# ap-pam-v3_1.net
KiCad netlist of a schematic drawn in Altium Designer
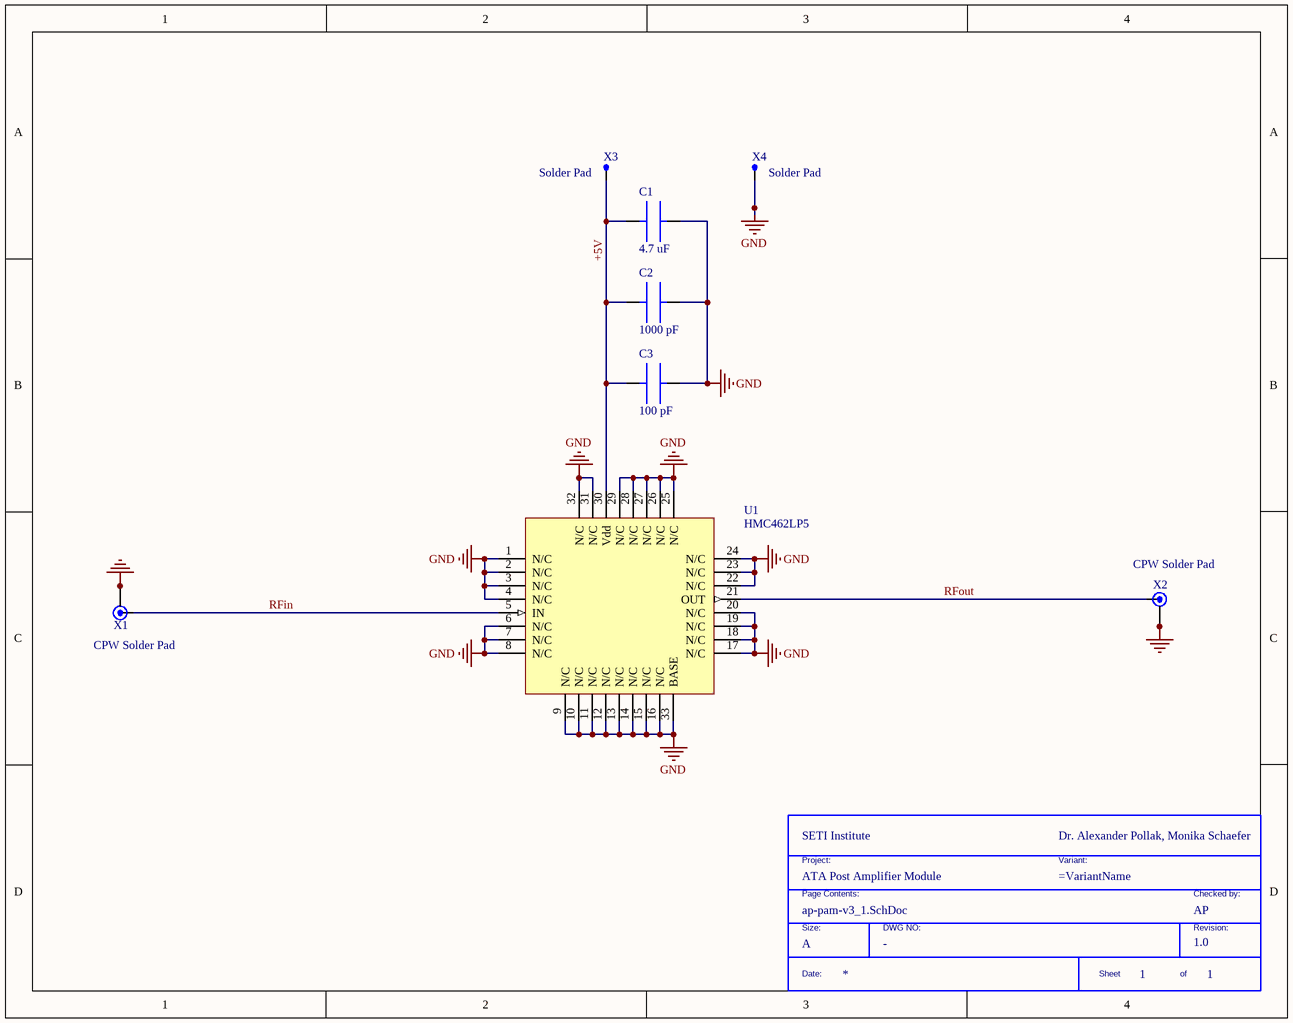
[diagram p0: ap-pam-v3_1.SchDoc]

(export (version "E")
  (design (tool "Eeschema 10.0.6"))
  (components
    (comp (ref "*")
      (value "~")
      (description "Standard Title Block")
      (fields (field (name "DWG NO") "-") (field (name "SIZE") "A") (field (name "CHECKED BY") "AP"))
      (libsource (lib "ap-pam") (part "TitleBlock"))
    )
    (comp (ref "C1")
      (value "4.7 uF")
      (footprint "C4_7uF")
      (fields
        (field (name "MANUFACTURER") "Vishay Sprague")
        (field (name "MANUFACTURER PART NUMBER") "TH3A475K010C2900")
      )
      (libsource (lib "ap-pam") (part "TH3A475K010C2900"))
    )
    (comp (ref "C2")
      (value "1000 pF")
      (footprint "C1000pF")
      (fields
        (field (name "MANUFACTURER") "Murata")
        (field (name "MANUFACTURER PART NUMBER") "GCM1885C1H102FA16D")
      )
      (libsource (lib "ap-pam") (part "GCM1885C1H102FA16D"))
    )
    (comp (ref "C3")
      (value "100 pF")
      (footprint "C100pF")
      (description "Multilayer Ceramic Capacitors MLCC - SMD/SMT 100 pF 100 VDC 1% 0402 C0G (NP0)")
      (fields
        (field (name "MANUFACTURER") "Murata")
        (field (name "MANUFACTURER PART NUMBER") "GRM1555C2A101FA01D")
      )
      (libsource (lib "ap-pam") (part "GRM1555C2A101FA01D"))
    )
    (comp (ref "U1")
      (value "HMC462LP5")
      (footprint "HMC462LP5E")
      (description "Wide Band Low Power Amplifier, 2000MHz Min, 20000MHz Max, 1 Func, GAAS")
      (fields (field (name "MANUFACTURER") "Analog Devices"))
      (libsource (lib "ap-pam") (part "HMC462LP5"))
    )
    (comp (ref "X1")
      (value "CPW Solder Pad")
      (footprint "CPW Edge Connector")
      (description "Solder pad for RF Coplanar Waveguide Rogers 4350B Thickness 0.020\" Copper 1oz")
      (libsource (lib "ap-pam") (part "RF  CPW Solder Pad"))
    )
    (comp (ref "X2")
      (value "CPW Solder Pad")
      (footprint "CPW Edge Connector")
      (description "Solder pad for RF Coplanar Waveguide Rogers 4350B Thickness 0.020\" Copper 1oz")
      (libsource (lib "ap-pam") (part "RF  CPW Solder Pad"))
    )
    (comp (ref "X3")
      (value "Solder Pad")
      (footprint "Solder Pad")
      (description "Pad to solder wires to")
      (libsource (lib "ap-pam") (part "Solder Pad"))
    )
    (comp (ref "X4")
      (value "Solder Pad")
      (footprint "Solder Pad")
      (description "Pad to solder wires to")
      (libsource (lib "ap-pam") (part "Solder Pad"))
    )
  )
  (nets
    (net (code "1") (name "/+5V") (class "Default")
      (node (ref "C1") (pin "1") (pinfunction "1_1") (pintype "passive"))
      (node (ref "C2") (pin "2") (pinfunction "2_2") (pintype "passive"))
      (node (ref "C3") (pin "2") (pinfunction "2_2") (pintype "passive"))
      (node (ref "U1") (pin "30") (pinfunction "Vdd_30") (pintype "power_in"))
      (node (ref "X3") (pin "1") (pinfunction "1_1") (pintype "passive"))
    )
    (net (code "2") (name "/RFin") (class "Default")
      (node (ref "U1") (pin "5") (pinfunction "IN_5") (pintype "input"))
      (node (ref "X1") (pin "1") (pinfunction "1_1") (pintype "passive"))
    )
    (net (code "3") (name "/RFout") (class "Default")
      (node (ref "U1") (pin "21") (pinfunction "OUT_21") (pintype "output"))
      (node (ref "X2") (pin "1") (pinfunction "1_1") (pintype "passive"))
    )
    (net (code "4") (name "GND") (class "Default")
      (node (ref "C1") (pin "2") (pinfunction "2_2") (pintype "passive"))
      (node (ref "C2") (pin "1") (pinfunction "1_1") (pintype "passive"))
      (node (ref "C3") (pin "1") (pinfunction "1_1") (pintype "passive"))
      (node (ref "U1") (pin "1") (pinfunction "N/C_1") (pintype "passive"))
      (node (ref "U1") (pin "10") (pinfunction "N/C_10") (pintype "passive"))
      (node (ref "U1") (pin "11") (pinfunction "N/C_11") (pintype "passive"))
      (node (ref "U1") (pin "12") (pinfunction "N/C_12") (pintype "passive"))
      (node (ref "U1") (pin "13") (pinfunction "N/C_13") (pintype "passive"))
      (node (ref "U1") (pin "14") (pinfunction "N/C_14") (pintype "passive"))
      (node (ref "U1") (pin "15") (pinfunction "N/C_15") (pintype "passive"))
      (node (ref "U1") (pin "16") (pinfunction "N/C_16") (pintype "passive"))
      (node (ref "U1") (pin "17") (pinfunction "N/C_17") (pintype "passive"))
      (node (ref "U1") (pin "18") (pinfunction "N/C_18") (pintype "passive"))
      (node (ref "U1") (pin "19") (pinfunction "N/C_19") (pintype "passive"))
      (node (ref "U1") (pin "2") (pinfunction "N/C_2") (pintype "passive"))
      (node (ref "U1") (pin "20") (pinfunction "N/C_20") (pintype "passive"))
      (node (ref "U1") (pin "22") (pinfunction "N/C_22") (pintype "passive"))
      (node (ref "U1") (pin "23") (pinfunction "N/C_23") (pintype "passive"))
      (node (ref "U1") (pin "24") (pinfunction "N/C_24") (pintype "passive"))
      (node (ref "U1") (pin "25") (pinfunction "N/C_25") (pintype "passive"))
      (node (ref "U1") (pin "26") (pinfunction "N/C_26") (pintype "passive"))
      (node (ref "U1") (pin "27") (pinfunction "N/C_27") (pintype "passive"))
      (node (ref "U1") (pin "28") (pinfunction "N/C_28") (pintype "passive"))
      (node (ref "U1") (pin "29") (pinfunction "N/C_29") (pintype "passive"))
      (node (ref "U1") (pin "3") (pinfunction "N/C_3") (pintype "passive"))
      (node (ref "U1") (pin "31") (pinfunction "N/C_31") (pintype "passive"))
      (node (ref "U1") (pin "32") (pinfunction "N/C_32") (pintype "passive"))
      (node (ref "U1") (pin "33") (pinfunction "BASE_33") (pintype "power_in"))
      (node (ref "U1") (pin "4") (pinfunction "N/C_4") (pintype "passive"))
      (node (ref "U1") (pin "6") (pinfunction "N/C_6") (pintype "passive"))
      (node (ref "U1") (pin "7") (pinfunction "N/C_7") (pintype "passive"))
      (node (ref "U1") (pin "8") (pinfunction "N/C_8") (pintype "passive"))
      (node (ref "U1") (pin "9") (pinfunction "N/C_9") (pintype "passive"))
      (node (ref "X1") (pin "2") (pinfunction "2_2") (pintype "passive"))
      (node (ref "X1") (pin "3") (pinfunction "3_3") (pintype "passive"))
      (node (ref "X2") (pin "2") (pinfunction "2_2") (pintype "passive"))
      (node (ref "X2") (pin "3") (pinfunction "3_3") (pintype "passive"))
      (node (ref "X4") (pin "1") (pinfunction "1_1") (pintype "passive"))
    )
  )
)
